# v01.net
KiCad netlist of a schematic drawn in EAGLE
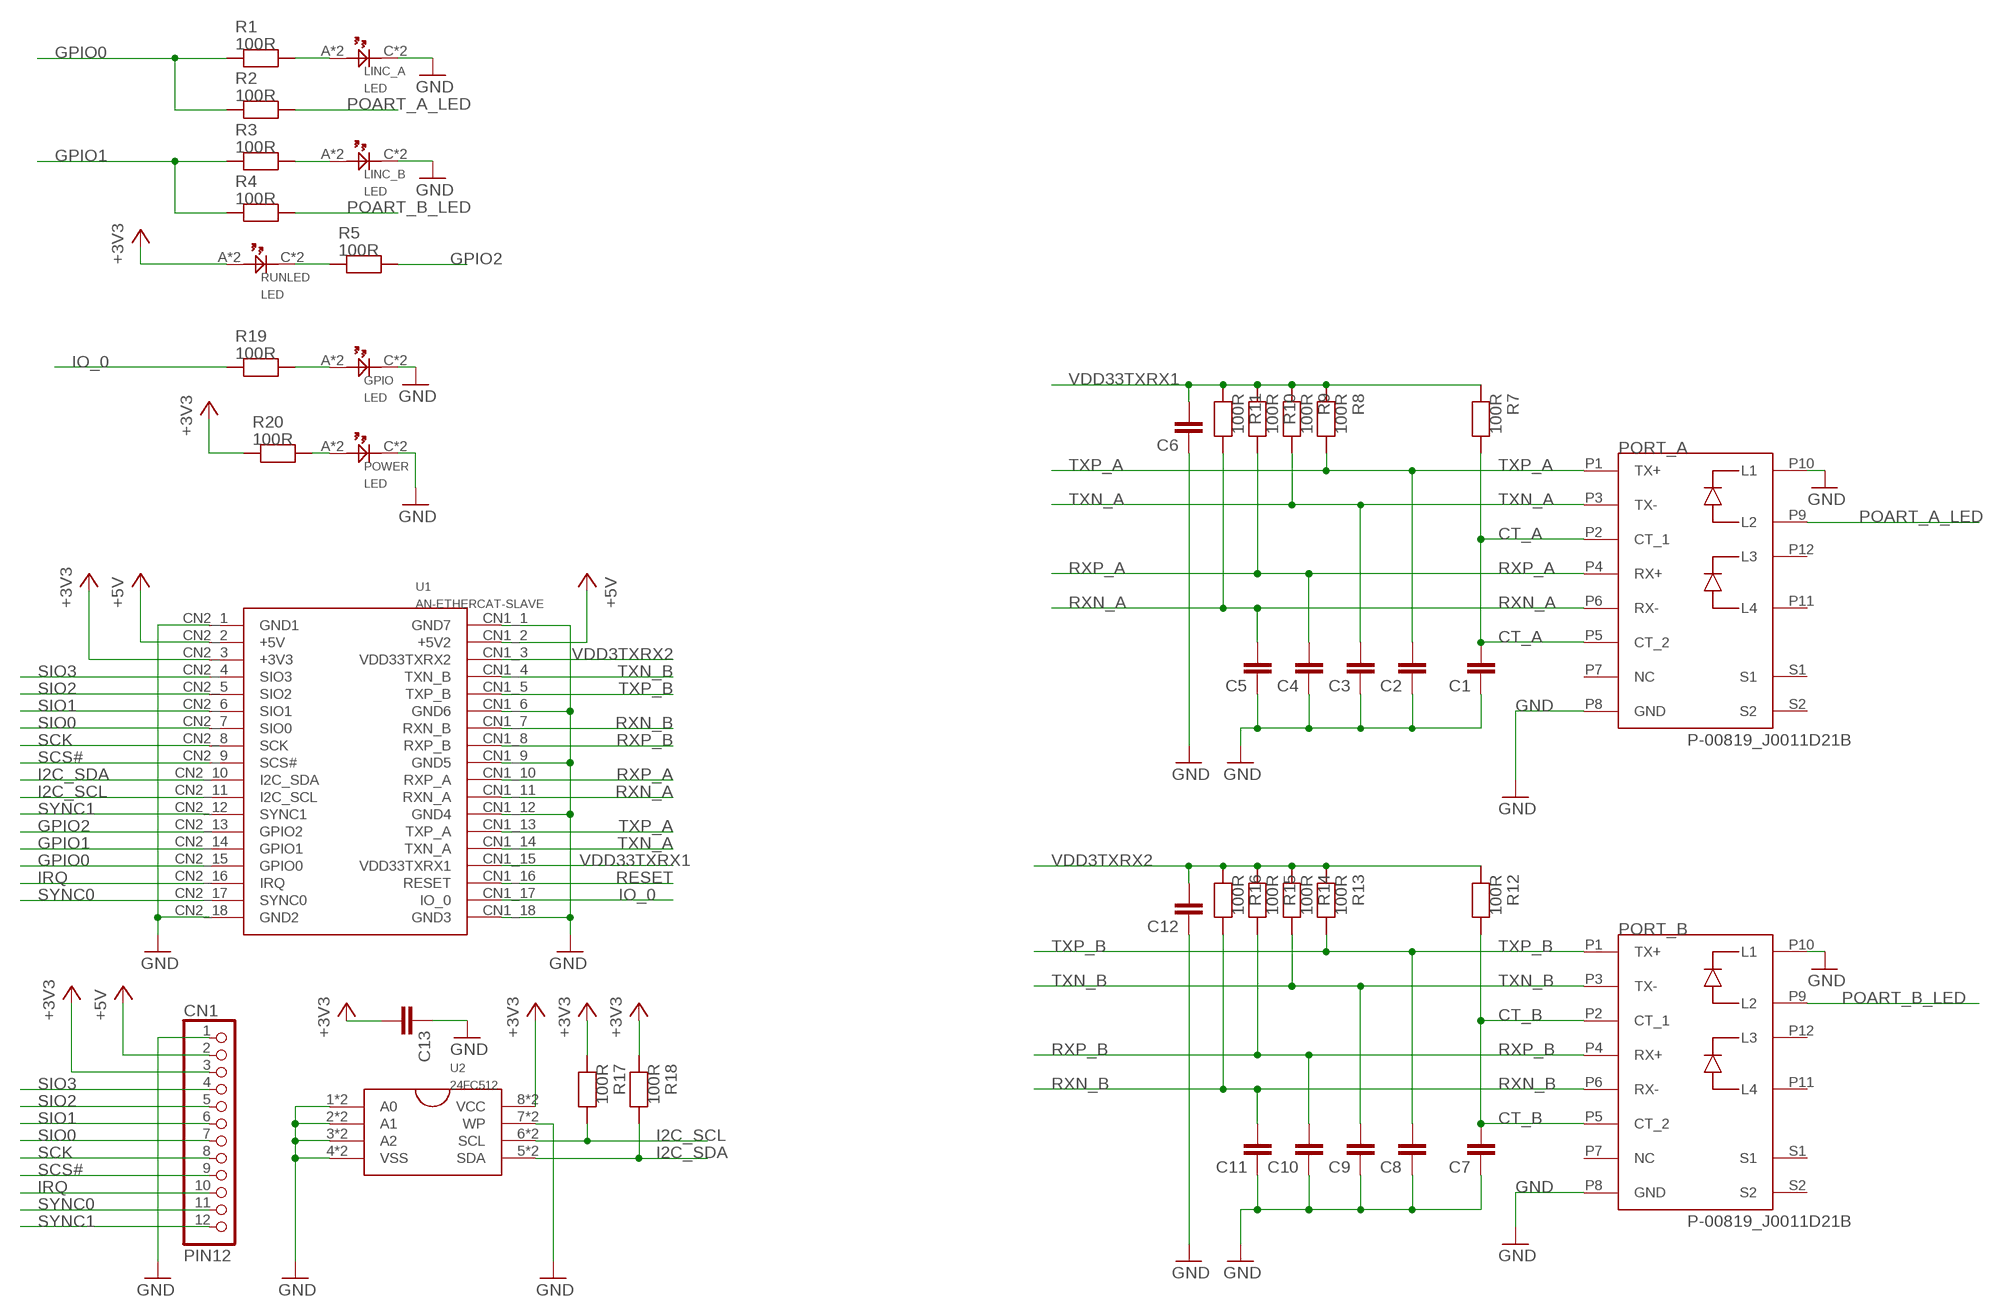
[diagram p0: schematic, sheet 1]

(export (version "E")
  (design (tool "Eeschema 10.0.6"))
  (components
    (comp (ref "C1")
      (value "C_1068")
      (footprint "eagle-import:C0603")
      (libsource (lib "eagle-import") (part "C_1068"))
    )
    (comp (ref "C2")
      (value "C_1068")
      (footprint "eagle-import:C0603")
      (libsource (lib "eagle-import") (part "C_1068"))
    )
    (comp (ref "C3")
      (value "C_1068")
      (footprint "eagle-import:C0603")
      (libsource (lib "eagle-import") (part "C_1068"))
    )
    (comp (ref "C4")
      (value "C_1068")
      (footprint "eagle-import:C0603")
      (libsource (lib "eagle-import") (part "C_1068"))
    )
    (comp (ref "C5")
      (value "C_1068")
      (footprint "eagle-import:C0603")
      (libsource (lib "eagle-import") (part "C_1068"))
    )
    (comp (ref "C6")
      (value "C_1068")
      (footprint "eagle-import:C0603")
      (libsource (lib "eagle-import") (part "C_1068"))
    )
    (comp (ref "C7")
      (value "C_1068")
      (footprint "eagle-import:C0603")
      (libsource (lib "eagle-import") (part "C_1068"))
    )
    (comp (ref "C8")
      (value "C_1068")
      (footprint "eagle-import:C0603")
      (libsource (lib "eagle-import") (part "C_1068"))
    )
    (comp (ref "C9")
      (value "C_1068")
      (footprint "eagle-import:C0603")
      (libsource (lib "eagle-import") (part "C_1068"))
    )
    (comp (ref "C10")
      (value "C_1068")
      (footprint "eagle-import:C0603")
      (libsource (lib "eagle-import") (part "C_1068"))
    )
    (comp (ref "C11")
      (value "C_1068")
      (footprint "eagle-import:C0603")
      (libsource (lib "eagle-import") (part "C_1068"))
    )
    (comp (ref "C12")
      (value "C_1068")
      (footprint "eagle-import:C0603")
      (libsource (lib "eagle-import") (part "C_1068"))
    )
    (comp (ref "C13")
      (value "C_1068")
      (footprint "eagle-import:C0603")
      (libsource (lib "eagle-import") (part "C_1068"))
    )
    (comp (ref "CN1")
      (value "PIN12")
      (footprint "eagle-import:PIN12")
      (libsource (lib "eagle-import") (part "PIN12"))
    )
    (comp (ref "GPIO")
      (value "LED")
      (footprint "eagle-import:CHIPLED_0805")
      (libsource (lib "eagle-import") (part "LED"))
    )
    (comp (ref "LINC_A")
      (value "LED")
      (footprint "eagle-import:CHIPLED_0805")
      (libsource (lib "eagle-import") (part "LED"))
    )
    (comp (ref "LINC_B")
      (value "LED")
      (footprint "eagle-import:CHIPLED_0805")
      (libsource (lib "eagle-import") (part "LED"))
    )
    (comp (ref "PORT_A")
      (value "P-00819_J0011D21B")
      (footprint "eagle-import:J0011D21B")
      (libsource (lib "eagle-import") (part "P-00819_J0011D21B"))
    )
    (comp (ref "PORT_B")
      (value "P-00819_J0011D21B")
      (footprint "eagle-import:J0011D21B")
      (libsource (lib "eagle-import") (part "P-00819_J0011D21B"))
    )
    (comp (ref "POWER")
      (value "LED")
      (footprint "eagle-import:CHIPLED_0805")
      (libsource (lib "eagle-import") (part "LED"))
    )
    (comp (ref "R1")
      (value "100R")
      (footprint "eagle-import:R0603")
      (libsource (lib "eagle-import") (part "R_1068"))
    )
    (comp (ref "R2")
      (value "100R")
      (footprint "eagle-import:R0603")
      (libsource (lib "eagle-import") (part "R_1068"))
    )
    (comp (ref "R3")
      (value "100R")
      (footprint "eagle-import:R0603")
      (libsource (lib "eagle-import") (part "R_1068"))
    )
    (comp (ref "R4")
      (value "100R")
      (footprint "eagle-import:R0603")
      (libsource (lib "eagle-import") (part "R_1068"))
    )
    (comp (ref "R5")
      (value "100R")
      (footprint "eagle-import:R0603")
      (libsource (lib "eagle-import") (part "R_1068"))
    )
    (comp (ref "R7")
      (value "100R")
      (footprint "eagle-import:R0603")
      (libsource (lib "eagle-import") (part "R_1068"))
    )
    (comp (ref "R8")
      (value "100R")
      (footprint "eagle-import:R0603")
      (libsource (lib "eagle-import") (part "R_1068"))
    )
    (comp (ref "R9")
      (value "100R")
      (footprint "eagle-import:R0603")
      (libsource (lib "eagle-import") (part "R_1068"))
    )
    (comp (ref "R10")
      (value "100R")
      (footprint "eagle-import:R0603")
      (libsource (lib "eagle-import") (part "R_1068"))
    )
    (comp (ref "R11")
      (value "100R")
      (footprint "eagle-import:R0603")
      (libsource (lib "eagle-import") (part "R_1068"))
    )
    (comp (ref "R12")
      (value "100R")
      (footprint "eagle-import:R0603")
      (libsource (lib "eagle-import") (part "R_1068"))
    )
    (comp (ref "R13")
      (value "100R")
      (footprint "eagle-import:R0603")
      (libsource (lib "eagle-import") (part "R_1068"))
    )
    (comp (ref "R14")
      (value "100R")
      (footprint "eagle-import:R0603")
      (libsource (lib "eagle-import") (part "R_1068"))
    )
    (comp (ref "R15")
      (value "100R")
      (footprint "eagle-import:R0603")
      (libsource (lib "eagle-import") (part "R_1068"))
    )
    (comp (ref "R16")
      (value "100R")
      (footprint "eagle-import:R0603")
      (libsource (lib "eagle-import") (part "R_1068"))
    )
    (comp (ref "R17")
      (value "100R")
      (footprint "eagle-import:R0603")
      (libsource (lib "eagle-import") (part "R_1068"))
    )
    (comp (ref "R18")
      (value "100R")
      (footprint "eagle-import:R0603")
      (libsource (lib "eagle-import") (part "R_1068"))
    )
    (comp (ref "R19")
      (value "100R")
      (footprint "eagle-import:R0603")
      (libsource (lib "eagle-import") (part "R_1068"))
    )
    (comp (ref "R20")
      (value "100R")
      (footprint "eagle-import:R0603")
      (libsource (lib "eagle-import") (part "R_1068"))
    )
    (comp (ref "RUNLED")
      (value "LED")
      (footprint "eagle-import:CHIPLED_0805")
      (libsource (lib "eagle-import") (part "LED"))
    )
    (comp (ref "U1")
      (value "AN-ETHERCAT-SLAVE")
      (footprint "eagle-import:AN-ETHERCAT-SLAVE")
      (libsource (lib "eagle-import") (part "AN-ETHERCAT-SLAVE"))
    )
    (comp (ref "U2")
      (value "24FC512")
      (footprint "eagle-import:SOP8")
      (libsource (lib "eagle-import") (part "24FC512"))
    )
  )
  (nets
    (net (code "1") (name "+3V3") (class "Default")
      (node (ref "C13") (pin "2") (pinfunction "2_2") (pintype "passive"))
      (node (ref "CN1") (pin "3") (pinfunction "3_3") (pintype "passive"))
      (node (ref "R17") (pin "1") (pinfunction "1_1") (pintype "bidirectional"))
      (node (ref "R18") (pin "1") (pinfunction "1_1") (pintype "bidirectional"))
      (node (ref "R20") (pin "1") (pinfunction "1_1") (pintype "bidirectional"))
      (node (ref "RUNLED") (pin "A") (pinfunction "A_A") (pintype "bidirectional"))
      (node (ref "RUNLED") (pin "DA") (pinfunction "A_DA") (pintype "bidirectional"))
      (node (ref "U1") (pin "CN2_3") (pinfunction "+3V3_CN2_3") (pintype "bidirectional"))
      (node (ref "U2") (pin "8") (pinfunction "VCC_8") (pintype "bidirectional"))
      (node (ref "U2") (pin "D8") (pinfunction "VCC_D8") (pintype "bidirectional"))
    )
    (net (code "2") (name "+5V") (class "Default")
      (node (ref "CN1") (pin "2") (pinfunction "2_2") (pintype "passive"))
      (node (ref "U1") (pin "CN1_2") (pinfunction "+5V2_CN1_2") (pintype "bidirectional"))
      (node (ref "U1") (pin "CN2_2") (pinfunction "+5V_CN2_2") (pintype "bidirectional"))
    )
    (net (code "3") (name "/CT_A") (class "Default")
      (node (ref "C1") (pin "2") (pinfunction "2_2") (pintype "passive"))
      (node (ref "PORT_A") (pin "P2") (pinfunction "CT_1_P2") (pintype "bidirectional"))
      (node (ref "PORT_A") (pin "P5") (pinfunction "CT_2_P5") (pintype "bidirectional"))
      (node (ref "R7") (pin "2") (pinfunction "2_2") (pintype "bidirectional"))
    )
    (net (code "4") (name "/CT_B") (class "Default")
      (node (ref "C7") (pin "2") (pinfunction "2_2") (pintype "passive"))
      (node (ref "PORT_B") (pin "P2") (pinfunction "CT_1_P2") (pintype "bidirectional"))
      (node (ref "PORT_B") (pin "P5") (pinfunction "CT_2_P5") (pintype "bidirectional"))
      (node (ref "R12") (pin "2") (pinfunction "2_2") (pintype "bidirectional"))
    )
    (net (code "5") (name "/GPIO0") (class "Default")
      (node (ref "R1") (pin "1") (pinfunction "1_1") (pintype "bidirectional"))
      (node (ref "R2") (pin "1") (pinfunction "1_1") (pintype "bidirectional"))
      (node (ref "U1") (pin "CN2_15") (pinfunction "GPIO0_CN2_15") (pintype "bidirectional"))
    )
    (net (code "6") (name "/GPIO1") (class "Default")
      (node (ref "R3") (pin "1") (pinfunction "1_1") (pintype "bidirectional"))
      (node (ref "R4") (pin "1") (pinfunction "1_1") (pintype "bidirectional"))
      (node (ref "U1") (pin "CN2_14") (pinfunction "GPIO1_CN2_14") (pintype "bidirectional"))
    )
    (net (code "7") (name "/GPIO2") (class "Default")
      (node (ref "R5") (pin "2") (pinfunction "2_2") (pintype "bidirectional"))
      (node (ref "U1") (pin "CN2_13") (pinfunction "GPIO2_CN2_13") (pintype "bidirectional"))
    )
    (net (code "8") (name "/I2C_SCL") (class "Default")
      (node (ref "R17") (pin "2") (pinfunction "2_2") (pintype "bidirectional"))
      (node (ref "U1") (pin "CN2_11") (pinfunction "I2C_SCL_CN2_11") (pintype "bidirectional"))
      (node (ref "U2") (pin "6") (pinfunction "SCL_6") (pintype "bidirectional"))
      (node (ref "U2") (pin "D6") (pinfunction "SCL_D6") (pintype "bidirectional"))
    )
    (net (code "9") (name "/I2C_SDA") (class "Default")
      (node (ref "R18") (pin "2") (pinfunction "2_2") (pintype "bidirectional"))
      (node (ref "U1") (pin "CN2_10") (pinfunction "I2C_SDA_CN2_10") (pintype "bidirectional"))
      (node (ref "U2") (pin "5") (pinfunction "SDA_5") (pintype "bidirectional"))
      (node (ref "U2") (pin "D5") (pinfunction "SDA_D5") (pintype "bidirectional"))
    )
    (net (code "10") (name "/IO_0") (class "Default")
      (node (ref "R19") (pin "1") (pinfunction "1_1") (pintype "bidirectional"))
      (node (ref "U1") (pin "CN1_17") (pinfunction "IO_0_CN1_17") (pintype "bidirectional"))
    )
    (net (code "11") (name "/IRQ") (class "Default")
      (node (ref "CN1") (pin "10") (pinfunction "10_10") (pintype "passive"))
      (node (ref "U1") (pin "CN2_16") (pinfunction "IRQ_CN2_16") (pintype "bidirectional"))
    )
    (net (code "12") (name "/POART_A_LED") (class "Default")
      (node (ref "PORT_A") (pin "P9") (pinfunction "L2_P9") (pintype "bidirectional"))
      (node (ref "R2") (pin "2") (pinfunction "2_2") (pintype "bidirectional"))
    )
    (net (code "13") (name "/POART_B_LED") (class "Default")
      (node (ref "PORT_B") (pin "P9") (pinfunction "L2_P9") (pintype "bidirectional"))
      (node (ref "R4") (pin "2") (pinfunction "2_2") (pintype "bidirectional"))
    )
    (net (code "14") (name "/RESET") (class "Default")
      (node (ref "U1") (pin "CN1_16") (pinfunction "RESET_CN1_16") (pintype "bidirectional"))
    )
    (net (code "15") (name "/RXN_A") (class "Default")
      (node (ref "C5") (pin "2") (pinfunction "2_2") (pintype "passive"))
      (node (ref "PORT_A") (pin "P6") (pinfunction "RX-_P6") (pintype "bidirectional"))
      (node (ref "R11") (pin "2") (pinfunction "2_2") (pintype "bidirectional"))
      (node (ref "U1") (pin "CN1_11") (pinfunction "RXN_A_CN1_11") (pintype "bidirectional"))
    )
    (net (code "16") (name "/RXN_B") (class "Default")
      (node (ref "C11") (pin "2") (pinfunction "2_2") (pintype "passive"))
      (node (ref "PORT_B") (pin "P6") (pinfunction "RX-_P6") (pintype "bidirectional"))
      (node (ref "R16") (pin "2") (pinfunction "2_2") (pintype "bidirectional"))
      (node (ref "U1") (pin "CN1_7") (pinfunction "RXN_B_CN1_7") (pintype "bidirectional"))
    )
    (net (code "17") (name "/RXP_A") (class "Default")
      (node (ref "C4") (pin "2") (pinfunction "2_2") (pintype "passive"))
      (node (ref "PORT_A") (pin "P4") (pinfunction "RX+_P4") (pintype "bidirectional"))
      (node (ref "R10") (pin "2") (pinfunction "2_2") (pintype "bidirectional"))
      (node (ref "U1") (pin "CN1_10") (pinfunction "RXP_A_CN1_10") (pintype "bidirectional"))
    )
    (net (code "18") (name "/RXP_B") (class "Default")
      (node (ref "C10") (pin "2") (pinfunction "2_2") (pintype "passive"))
      (node (ref "PORT_B") (pin "P4") (pinfunction "RX+_P4") (pintype "bidirectional"))
      (node (ref "R15") (pin "2") (pinfunction "2_2") (pintype "bidirectional"))
      (node (ref "U1") (pin "CN1_8") (pinfunction "RXP_B_CN1_8") (pintype "bidirectional"))
    )
    (net (code "19") (name "/SCK") (class "Default")
      (node (ref "CN1") (pin "8") (pinfunction "8_8") (pintype "passive"))
      (node (ref "U1") (pin "CN2_8") (pinfunction "SCK_CN2_8") (pintype "bidirectional"))
    )
    (net (code "20") (name "/SCS#") (class "Default")
      (node (ref "CN1") (pin "9") (pinfunction "9_9") (pintype "passive"))
      (node (ref "U1") (pin "CN2_9") (pinfunction "SCS#_CN2_9") (pintype "bidirectional"))
    )
    (net (code "21") (name "/SIO0") (class "Default")
      (node (ref "CN1") (pin "7") (pinfunction "7_7") (pintype "passive"))
      (node (ref "U1") (pin "CN2_7") (pinfunction "SIO0_CN2_7") (pintype "bidirectional"))
    )
    (net (code "22") (name "/SIO1") (class "Default")
      (node (ref "CN1") (pin "6") (pinfunction "6_6") (pintype "passive"))
      (node (ref "U1") (pin "CN2_6") (pinfunction "SIO1_CN2_6") (pintype "bidirectional"))
    )
    (net (code "23") (name "/SIO2") (class "Default")
      (node (ref "CN1") (pin "5") (pinfunction "5_5") (pintype "passive"))
      (node (ref "U1") (pin "CN2_5") (pinfunction "SIO2_CN2_5") (pintype "bidirectional"))
    )
    (net (code "24") (name "/SIO3") (class "Default")
      (node (ref "CN1") (pin "4") (pinfunction "4_4") (pintype "passive"))
      (node (ref "U1") (pin "CN2_4") (pinfunction "SIO3_CN2_4") (pintype "bidirectional"))
    )
    (net (code "25") (name "/SYNC0") (class "Default")
      (node (ref "CN1") (pin "11") (pinfunction "11_11") (pintype "passive"))
      (node (ref "U1") (pin "CN2_17") (pinfunction "SYNC0_CN2_17") (pintype "bidirectional"))
    )
    (net (code "26") (name "/SYNC1") (class "Default")
      (node (ref "CN1") (pin "12") (pinfunction "12_12") (pintype "passive"))
      (node (ref "U1") (pin "CN2_12") (pinfunction "SYNC1_CN2_12") (pintype "bidirectional"))
    )
    (net (code "27") (name "/TXN_A") (class "Default")
      (node (ref "C3") (pin "2") (pinfunction "2_2") (pintype "passive"))
      (node (ref "PORT_A") (pin "P3") (pinfunction "TX-_P3") (pintype "bidirectional"))
      (node (ref "R9") (pin "2") (pinfunction "2_2") (pintype "bidirectional"))
      (node (ref "U1") (pin "CN1_14") (pinfunction "TXN_A_CN1_14") (pintype "bidirectional"))
    )
    (net (code "28") (name "/TXN_B") (class "Default")
      (node (ref "C9") (pin "2") (pinfunction "2_2") (pintype "passive"))
      (node (ref "PORT_B") (pin "P3") (pinfunction "TX-_P3") (pintype "bidirectional"))
      (node (ref "R14") (pin "2") (pinfunction "2_2") (pintype "bidirectional"))
      (node (ref "U1") (pin "CN1_4") (pinfunction "TXN_B_CN1_4") (pintype "bidirectional"))
    )
    (net (code "29") (name "/TXP_A") (class "Default")
      (node (ref "C2") (pin "2") (pinfunction "2_2") (pintype "passive"))
      (node (ref "PORT_A") (pin "P1") (pinfunction "TX+_P1") (pintype "bidirectional"))
      (node (ref "R8") (pin "2") (pinfunction "2_2") (pintype "bidirectional"))
      (node (ref "U1") (pin "CN1_13") (pinfunction "TXP_A_CN1_13") (pintype "bidirectional"))
    )
    (net (code "30") (name "/TXP_B") (class "Default")
      (node (ref "C8") (pin "2") (pinfunction "2_2") (pintype "passive"))
      (node (ref "PORT_B") (pin "P1") (pinfunction "TX+_P1") (pintype "bidirectional"))
      (node (ref "R13") (pin "2") (pinfunction "2_2") (pintype "bidirectional"))
      (node (ref "U1") (pin "CN1_5") (pinfunction "TXP_B_CN1_5") (pintype "bidirectional"))
    )
    (net (code "31") (name "/VDD3TXRX2") (class "Default")
      (node (ref "C12") (pin "2") (pinfunction "2_2") (pintype "passive"))
      (node (ref "R12") (pin "1") (pinfunction "1_1") (pintype "bidirectional"))
      (node (ref "R13") (pin "1") (pinfunction "1_1") (pintype "bidirectional"))
      (node (ref "R14") (pin "1") (pinfunction "1_1") (pintype "bidirectional"))
      (node (ref "R15") (pin "1") (pinfunction "1_1") (pintype "bidirectional"))
      (node (ref "R16") (pin "1") (pinfunction "1_1") (pintype "bidirectional"))
      (node (ref "U1") (pin "CN1_3") (pinfunction "VDD33TXRX2_CN1_3") (pintype "bidirectional"))
    )
    (net (code "32") (name "/VDD33TXRX1") (class "Default")
      (node (ref "C6") (pin "2") (pinfunction "2_2") (pintype "passive"))
      (node (ref "R10") (pin "1") (pinfunction "1_1") (pintype "bidirectional"))
      (node (ref "R11") (pin "1") (pinfunction "1_1") (pintype "bidirectional"))
      (node (ref "R7") (pin "1") (pinfunction "1_1") (pintype "bidirectional"))
      (node (ref "R8") (pin "1") (pinfunction "1_1") (pintype "bidirectional"))
      (node (ref "R9") (pin "1") (pinfunction "1_1") (pintype "bidirectional"))
      (node (ref "U1") (pin "CN1_15") (pinfunction "VDD33TXRX1_CN1_15") (pintype "bidirectional"))
    )
    (net (code "33") (name "GND") (class "Default")
      (node (ref "C1") (pin "1") (pinfunction "1_1") (pintype "passive"))
      (node (ref "C10") (pin "1") (pinfunction "1_1") (pintype "passive"))
      (node (ref "C11") (pin "1") (pinfunction "1_1") (pintype "passive"))
      (node (ref "C12") (pin "1") (pinfunction "1_1") (pintype "passive"))
      (node (ref "C13") (pin "1") (pinfunction "1_1") (pintype "passive"))
      (node (ref "C2") (pin "1") (pinfunction "1_1") (pintype "passive"))
      (node (ref "C3") (pin "1") (pinfunction "1_1") (pintype "passive"))
      (node (ref "C4") (pin "1") (pinfunction "1_1") (pintype "passive"))
      (node (ref "C5") (pin "1") (pinfunction "1_1") (pintype "passive"))
      (node (ref "C6") (pin "1") (pinfunction "1_1") (pintype "passive"))
      (node (ref "C7") (pin "1") (pinfunction "1_1") (pintype "passive"))
      (node (ref "C8") (pin "1") (pinfunction "1_1") (pintype "passive"))
      (node (ref "C9") (pin "1") (pinfunction "1_1") (pintype "passive"))
      (node (ref "CN1") (pin "1") (pinfunction "1_1") (pintype "passive"))
      (node (ref "GPIO") (pin "C") (pinfunction "C_C") (pintype "bidirectional"))
      (node (ref "GPIO") (pin "DC") (pinfunction "C_DC") (pintype "bidirectional"))
      (node (ref "LINC_A") (pin "C") (pinfunction "C_C") (pintype "bidirectional"))
      (node (ref "LINC_A") (pin "DC") (pinfunction "C_DC") (pintype "bidirectional"))
      (node (ref "LINC_B") (pin "C") (pinfunction "C_C") (pintype "bidirectional"))
      (node (ref "LINC_B") (pin "DC") (pinfunction "C_DC") (pintype "bidirectional"))
      (node (ref "PORT_A") (pin "P10") (pinfunction "L1_P10") (pintype "bidirectional"))
      (node (ref "PORT_A") (pin "P8") (pinfunction "GND_P8") (pintype "bidirectional"))
      (node (ref "PORT_B") (pin "P10") (pinfunction "L1_P10") (pintype "bidirectional"))
      (node (ref "PORT_B") (pin "P8") (pinfunction "GND_P8") (pintype "bidirectional"))
      (node (ref "POWER") (pin "C") (pinfunction "C_C") (pintype "bidirectional"))
      (node (ref "POWER") (pin "DC") (pinfunction "C_DC") (pintype "bidirectional"))
      (node (ref "U1") (pin "CN1_1") (pinfunction "GND7_CN1_1") (pintype "bidirectional"))
      (node (ref "U1") (pin "CN1_12") (pinfunction "GND4_CN1_12") (pintype "bidirectional"))
      (node (ref "U1") (pin "CN1_18") (pinfunction "GND3_CN1_18") (pintype "bidirectional"))
      (node (ref "U1") (pin "CN1_6") (pinfunction "GND6_CN1_6") (pintype "bidirectional"))
      (node (ref "U1") (pin "CN1_9") (pinfunction "GND5_CN1_9") (pintype "bidirectional"))
      (node (ref "U1") (pin "CN2_1") (pinfunction "GND1_CN2_1") (pintype "bidirectional"))
      (node (ref "U1") (pin "CN2_18") (pinfunction "GND2_CN2_18") (pintype "bidirectional"))
      (node (ref "U2") (pin "1") (pinfunction "A0_1") (pintype "bidirectional"))
      (node (ref "U2") (pin "2") (pinfunction "A1_2") (pintype "bidirectional"))
      (node (ref "U2") (pin "3") (pinfunction "A2_3") (pintype "bidirectional"))
      (node (ref "U2") (pin "4") (pinfunction "VSS_4") (pintype "bidirectional"))
      (node (ref "U2") (pin "7") (pinfunction "WP_7") (pintype "bidirectional"))
      (node (ref "U2") (pin "D1") (pinfunction "A0_D1") (pintype "bidirectional"))
      (node (ref "U2") (pin "D2") (pinfunction "A1_D2") (pintype "bidirectional"))
      (node (ref "U2") (pin "D3") (pinfunction "A2_D3") (pintype "bidirectional"))
      (node (ref "U2") (pin "D4") (pinfunction "VSS_D4") (pintype "bidirectional"))
      (node (ref "U2") (pin "D7") (pinfunction "WP_D7") (pintype "bidirectional"))
    )
    (net (code "34") (name "Net-(GPIO-A-PadDA)") (class "Default")
      (node (ref "GPIO") (pin "A") (pinfunction "A_A") (pintype "bidirectional"))
      (node (ref "GPIO") (pin "DA") (pinfunction "A_DA") (pintype "bidirectional"))
      (node (ref "R19") (pin "2") (pinfunction "2_2") (pintype "bidirectional"))
    )
    (net (code "35") (name "Net-(LINC_A-A-PadDA)") (class "Default")
      (node (ref "LINC_A") (pin "A") (pinfunction "A_A") (pintype "bidirectional"))
      (node (ref "LINC_A") (pin "DA") (pinfunction "A_DA") (pintype "bidirectional"))
      (node (ref "R1") (pin "2") (pinfunction "2_2") (pintype "bidirectional"))
    )
    (net (code "36") (name "Net-(LINC_B-A-PadDA)") (class "Default")
      (node (ref "LINC_B") (pin "A") (pinfunction "A_A") (pintype "bidirectional"))
      (node (ref "LINC_B") (pin "DA") (pinfunction "A_DA") (pintype "bidirectional"))
      (node (ref "R3") (pin "2") (pinfunction "2_2") (pintype "bidirectional"))
    )
    (net (code "37") (name "Net-(POWER-A-PadDA)") (class "Default")
      (node (ref "POWER") (pin "A") (pinfunction "A_A") (pintype "bidirectional"))
      (node (ref "POWER") (pin "DA") (pinfunction "A_DA") (pintype "bidirectional"))
      (node (ref "R20") (pin "2") (pinfunction "2_2") (pintype "bidirectional"))
    )
    (net (code "38") (name "Net-(R5-Pad1)") (class "Default")
      (node (ref "R5") (pin "1") (pinfunction "1_1") (pintype "bidirectional"))
      (node (ref "RUNLED") (pin "C") (pinfunction "C_C") (pintype "bidirectional"))
      (node (ref "RUNLED") (pin "DC") (pinfunction "C_DC") (pintype "bidirectional"))
    )
    (net (code "39") (name "unconnected-(PORT_A-L3-PadP12)") (class "Default")
      (node (ref "PORT_A") (pin "P12") (pinfunction "L3_P12") (pintype "bidirectional"))
    )
    (net (code "40") (name "unconnected-(PORT_A-L4-PadP11)") (class "Default")
      (node (ref "PORT_A") (pin "P11") (pinfunction "L4_P11") (pintype "bidirectional"))
    )
    (net (code "41") (name "unconnected-(PORT_A-NC-PadP7)") (class "Default")
      (node (ref "PORT_A") (pin "P7") (pinfunction "NC_P7") (pintype "bidirectional"))
    )
    (net (code "42") (name "unconnected-(PORT_A-PadS1)") (class "Default")
      (node (ref "PORT_A") (pin "S1") (pinfunction "S1_S1") (pintype "bidirectional"))
    )
    (net (code "43") (name "unconnected-(PORT_A-PadS2)") (class "Default")
      (node (ref "PORT_A") (pin "S2") (pinfunction "S2_S2") (pintype "bidirectional"))
    )
    (net (code "44") (name "unconnected-(PORT_B-L3-PadP12)") (class "Default")
      (node (ref "PORT_B") (pin "P12") (pinfunction "L3_P12") (pintype "bidirectional"))
    )
    (net (code "45") (name "unconnected-(PORT_B-L4-PadP11)") (class "Default")
      (node (ref "PORT_B") (pin "P11") (pinfunction "L4_P11") (pintype "bidirectional"))
    )
    (net (code "46") (name "unconnected-(PORT_B-NC-PadP7)") (class "Default")
      (node (ref "PORT_B") (pin "P7") (pinfunction "NC_P7") (pintype "bidirectional"))
    )
    (net (code "47") (name "unconnected-(PORT_B-PadS1)") (class "Default")
      (node (ref "PORT_B") (pin "S1") (pinfunction "S1_S1") (pintype "bidirectional"))
    )
    (net (code "48") (name "unconnected-(PORT_B-PadS2)") (class "Default")
      (node (ref "PORT_B") (pin "S2") (pinfunction "S2_S2") (pintype "bidirectional"))
    )
  )
)
